# electrotactile_adapter.net
KiCad netlist of a schematic drawn in EAGLE
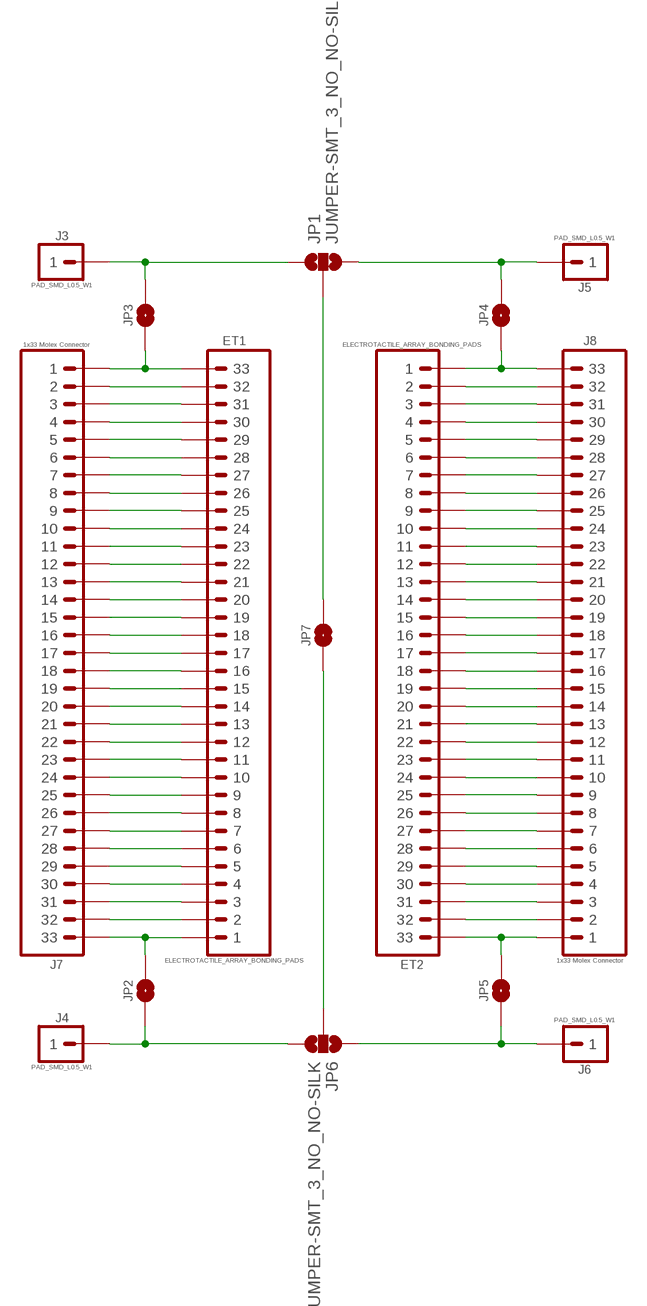
[diagram p0: schematic, sheet 1]

(export (version "E")
  (design (tool "Eeschema 10.0.6"))
  (components
    (comp (ref "ET1")
      (value "ELECTROTACTILE_ARRAY_BONDING_PADS")
      (footprint "eagle-import:ELECTROTACTILE_ARRAY_BONDING_PADS")
      (libsource (lib "eagle-import") (part "ELECTROTACTILE_ARRAY_BONDING_PADS"))
    )
    (comp (ref "ET2")
      (value "ELECTROTACTILE_ARRAY_BONDING_PADS")
      (footprint "eagle-import:ELECTROTACTILE_ARRAY_BONDING_PADS")
      (libsource (lib "eagle-import") (part "ELECTROTACTILE_ARRAY_BONDING_PADS"))
    )
    (comp (ref "J3")
      (value "PAD_SMD_L0.5_W1")
      (footprint "eagle-import:1X01_SMD_L0.5-W1")
      (libsource (lib "eagle-import") (part "PAD_SMD_L0.5_W1"))
    )
    (comp (ref "J4")
      (value "PAD_SMD_L0.5_W1")
      (footprint "eagle-import:1X01_SMD_L0.5-W1")
      (libsource (lib "eagle-import") (part "PAD_SMD_L0.5_W1"))
    )
    (comp (ref "J5")
      (value "PAD_SMD_L0.5_W1")
      (footprint "eagle-import:1X01_SMD_L0.5-W1")
      (libsource (lib "eagle-import") (part "PAD_SMD_L0.5_W1"))
    )
    (comp (ref "J6")
      (value "PAD_SMD_L0.5_W1")
      (footprint "eagle-import:1X01_SMD_L0.5-W1")
      (libsource (lib "eagle-import") (part "PAD_SMD_L0.5_W1"))
    )
    (comp (ref "J7")
      (value "1x33 Molex Connector")
      (footprint "eagle-import:_MOLEX-5025983393_FPC_PITCH-0.3MM")
      (fields (field (name "MFR") "Molex, LLC") (field (name "MPN") "5025983393"))
      (libsource (lib "eagle-import") (part "1X33_MOLEX_FPC_FPC_RIBBON-CABLE"))
    )
    (comp (ref "J8")
      (value "1x33 Molex Connector")
      (footprint "eagle-import:_MOLEX-5025983393_FPC_PITCH-0.3MM")
      (fields (field (name "MFR") "Molex, LLC") (field (name "MPN") "5025983393"))
      (libsource (lib "eagle-import") (part "1X33_MOLEX_FPC_FPC_RIBBON-CABLE"))
    )
    (comp (ref "JP1")
      (value "JUMPER-SMT_3_NO_NO-SILK")
      (footprint "eagle-import:SMT-JUMPER_3_NO_NO-SILK")
      (libsource (lib "eagle-import") (part "JUMPER-SMT_3_NO_NO-SILK"))
    )
    (comp (ref "JP2")
      (value "JUMPER_SMD_2-PAD_NO_SILK")
      (footprint "eagle-import:SMT-JUMPER_2_NO_SILK")
      (libsource (lib "eagle-import") (part "JUMPER_SMD_2-PAD_NO_SILK"))
    )
    (comp (ref "JP3")
      (value "JUMPER_SMD_2-PAD_NO_SILK")
      (footprint "eagle-import:SMT-JUMPER_2_NO_SILK")
      (libsource (lib "eagle-import") (part "JUMPER_SMD_2-PAD_NO_SILK"))
    )
    (comp (ref "JP4")
      (value "JUMPER_SMD_2-PAD_NO_SILK")
      (footprint "eagle-import:SMT-JUMPER_2_NO_SILK")
      (libsource (lib "eagle-import") (part "JUMPER_SMD_2-PAD_NO_SILK"))
    )
    (comp (ref "JP5")
      (value "JUMPER_SMD_2-PAD_NO_SILK")
      (footprint "eagle-import:SMT-JUMPER_2_NO_SILK")
      (libsource (lib "eagle-import") (part "JUMPER_SMD_2-PAD_NO_SILK"))
    )
    (comp (ref "JP6")
      (value "JUMPER-SMT_3_NO_NO-SILK")
      (footprint "eagle-import:SMT-JUMPER_3_NO_NO-SILK")
      (libsource (lib "eagle-import") (part "JUMPER-SMT_3_NO_NO-SILK"))
    )
    (comp (ref "JP7")
      (value "JUMPER_SMD_2-PAD_NO_SILK")
      (footprint "eagle-import:SMT-JUMPER_2_NO_SILK")
      (libsource (lib "eagle-import") (part "JUMPER_SMD_2-PAD_NO_SILK"))
    )
  )
  (nets
    (net (code "1") (name "Net-(ET1-1)") (class "Default")
      (node (ref "ET1") (pin "P$1") (pinfunction "1_P$1") (pintype "passive"))
      (node (ref "J7") (pin "P$33") (pinfunction "33_P$33") (pintype "passive"))
      (node (ref "JP2") (pin "2") (pinfunction "2_2") (pintype "passive"))
    )
    (net (code "2") (name "Net-(ET1-2)") (class "Default")
      (node (ref "ET1") (pin "P$2") (pinfunction "2_P$2") (pintype "passive"))
      (node (ref "J7") (pin "P$32") (pinfunction "32_P$32") (pintype "passive"))
    )
    (net (code "3") (name "Net-(ET1-3)") (class "Default")
      (node (ref "ET1") (pin "P$3") (pinfunction "3_P$3") (pintype "passive"))
      (node (ref "J7") (pin "P$31") (pinfunction "31_P$31") (pintype "passive"))
    )
    (net (code "4") (name "Net-(ET1-4)") (class "Default")
      (node (ref "ET1") (pin "P$4") (pinfunction "4_P$4") (pintype "passive"))
      (node (ref "J7") (pin "P$30") (pinfunction "30_P$30") (pintype "passive"))
    )
    (net (code "5") (name "Net-(ET1-5)") (class "Default")
      (node (ref "ET1") (pin "P$5") (pinfunction "5_P$5") (pintype "passive"))
      (node (ref "J7") (pin "P$29") (pinfunction "29_P$29") (pintype "passive"))
    )
    (net (code "6") (name "Net-(ET1-6)") (class "Default")
      (node (ref "ET1") (pin "P$6") (pinfunction "6_P$6") (pintype "passive"))
      (node (ref "J7") (pin "P$28") (pinfunction "28_P$28") (pintype "passive"))
    )
    (net (code "7") (name "Net-(ET1-7)") (class "Default")
      (node (ref "ET1") (pin "P$7") (pinfunction "7_P$7") (pintype "passive"))
      (node (ref "J7") (pin "P$27") (pinfunction "27_P$27") (pintype "passive"))
    )
    (net (code "8") (name "Net-(ET1-8)") (class "Default")
      (node (ref "ET1") (pin "P$8") (pinfunction "8_P$8") (pintype "passive"))
      (node (ref "J7") (pin "P$26") (pinfunction "26_P$26") (pintype "passive"))
    )
    (net (code "9") (name "Net-(ET1-9)") (class "Default")
      (node (ref "ET1") (pin "P$9") (pinfunction "9_P$9") (pintype "passive"))
      (node (ref "J7") (pin "P$25") (pinfunction "25_P$25") (pintype "passive"))
    )
    (net (code "10") (name "Net-(ET1-10)") (class "Default")
      (node (ref "ET1") (pin "P$10") (pinfunction "10_P$10") (pintype "passive"))
      (node (ref "J7") (pin "P$24") (pinfunction "24_P$24") (pintype "passive"))
    )
    (net (code "11") (name "Net-(ET1-11)") (class "Default")
      (node (ref "ET1") (pin "P$11") (pinfunction "11_P$11") (pintype "passive"))
      (node (ref "J7") (pin "P$23") (pinfunction "23_P$23") (pintype "passive"))
    )
    (net (code "12") (name "Net-(ET1-12)") (class "Default")
      (node (ref "ET1") (pin "P$12") (pinfunction "12_P$12") (pintype "passive"))
      (node (ref "J7") (pin "P$22") (pinfunction "22_P$22") (pintype "passive"))
    )
    (net (code "13") (name "Net-(ET1-13)") (class "Default")
      (node (ref "ET1") (pin "P$13") (pinfunction "13_P$13") (pintype "passive"))
      (node (ref "J7") (pin "P$21") (pinfunction "21_P$21") (pintype "passive"))
    )
    (net (code "14") (name "Net-(ET1-14)") (class "Default")
      (node (ref "ET1") (pin "P$14") (pinfunction "14_P$14") (pintype "passive"))
      (node (ref "J7") (pin "P$20") (pinfunction "20_P$20") (pintype "passive"))
    )
    (net (code "15") (name "Net-(ET1-15)") (class "Default")
      (node (ref "ET1") (pin "P$15") (pinfunction "15_P$15") (pintype "passive"))
      (node (ref "J7") (pin "P$19") (pinfunction "19_P$19") (pintype "passive"))
    )
    (net (code "16") (name "Net-(ET1-16)") (class "Default")
      (node (ref "ET1") (pin "P$16") (pinfunction "16_P$16") (pintype "passive"))
      (node (ref "J7") (pin "P$18") (pinfunction "18_P$18") (pintype "passive"))
    )
    (net (code "17") (name "Net-(ET1-17)") (class "Default")
      (node (ref "ET1") (pin "P$17") (pinfunction "17_P$17") (pintype "passive"))
      (node (ref "J7") (pin "P$17") (pinfunction "17_P$17") (pintype "passive"))
    )
    (net (code "18") (name "Net-(ET1-18)") (class "Default")
      (node (ref "ET1") (pin "P$18") (pinfunction "18_P$18") (pintype "passive"))
      (node (ref "J7") (pin "P$16") (pinfunction "16_P$16") (pintype "passive"))
    )
    (net (code "19") (name "Net-(ET1-19)") (class "Default")
      (node (ref "ET1") (pin "P$19") (pinfunction "19_P$19") (pintype "passive"))
      (node (ref "J7") (pin "P$15") (pinfunction "15_P$15") (pintype "passive"))
    )
    (net (code "20") (name "Net-(ET1-20)") (class "Default")
      (node (ref "ET1") (pin "P$20") (pinfunction "20_P$20") (pintype "passive"))
      (node (ref "J7") (pin "P$14") (pinfunction "14_P$14") (pintype "passive"))
    )
    (net (code "21") (name "Net-(ET1-21)") (class "Default")
      (node (ref "ET1") (pin "P$21") (pinfunction "21_P$21") (pintype "passive"))
      (node (ref "J7") (pin "P$13") (pinfunction "13_P$13") (pintype "passive"))
    )
    (net (code "22") (name "Net-(ET1-22)") (class "Default")
      (node (ref "ET1") (pin "P$22") (pinfunction "22_P$22") (pintype "passive"))
      (node (ref "J7") (pin "P$12") (pinfunction "12_P$12") (pintype "passive"))
    )
    (net (code "23") (name "Net-(ET1-23)") (class "Default")
      (node (ref "ET1") (pin "P$23") (pinfunction "23_P$23") (pintype "passive"))
      (node (ref "J7") (pin "P$11") (pinfunction "11_P$11") (pintype "passive"))
    )
    (net (code "24") (name "Net-(ET1-24)") (class "Default")
      (node (ref "ET1") (pin "P$24") (pinfunction "24_P$24") (pintype "passive"))
      (node (ref "J7") (pin "P$10") (pinfunction "10_P$10") (pintype "passive"))
    )
    (net (code "25") (name "Net-(ET1-25)") (class "Default")
      (node (ref "ET1") (pin "P$25") (pinfunction "25_P$25") (pintype "passive"))
      (node (ref "J7") (pin "P$9") (pinfunction "9_P$9") (pintype "passive"))
    )
    (net (code "26") (name "Net-(ET1-26)") (class "Default")
      (node (ref "ET1") (pin "P$26") (pinfunction "26_P$26") (pintype "passive"))
      (node (ref "J7") (pin "P$8") (pinfunction "8_P$8") (pintype "passive"))
    )
    (net (code "27") (name "Net-(ET1-27)") (class "Default")
      (node (ref "ET1") (pin "P$27") (pinfunction "27_P$27") (pintype "passive"))
      (node (ref "J7") (pin "P$7") (pinfunction "7_P$7") (pintype "passive"))
    )
    (net (code "28") (name "Net-(ET1-28)") (class "Default")
      (node (ref "ET1") (pin "P$28") (pinfunction "28_P$28") (pintype "passive"))
      (node (ref "J7") (pin "P$6") (pinfunction "6_P$6") (pintype "passive"))
    )
    (net (code "29") (name "Net-(ET1-29)") (class "Default")
      (node (ref "ET1") (pin "P$29") (pinfunction "29_P$29") (pintype "passive"))
      (node (ref "J7") (pin "P$5") (pinfunction "5_P$5") (pintype "passive"))
    )
    (net (code "30") (name "Net-(ET1-30)") (class "Default")
      (node (ref "ET1") (pin "P$30") (pinfunction "30_P$30") (pintype "passive"))
      (node (ref "J7") (pin "P$4") (pinfunction "4_P$4") (pintype "passive"))
    )
    (net (code "31") (name "Net-(ET1-31)") (class "Default")
      (node (ref "ET1") (pin "P$31") (pinfunction "31_P$31") (pintype "passive"))
      (node (ref "J7") (pin "P$3") (pinfunction "3_P$3") (pintype "passive"))
    )
    (net (code "32") (name "Net-(ET1-32)") (class "Default")
      (node (ref "ET1") (pin "P$32") (pinfunction "32_P$32") (pintype "passive"))
      (node (ref "J7") (pin "P$2") (pinfunction "2_P$2") (pintype "passive"))
    )
    (net (code "33") (name "Net-(ET1-33)") (class "Default")
      (node (ref "ET1") (pin "P$33") (pinfunction "33_P$33") (pintype "passive"))
      (node (ref "J7") (pin "P$1") (pinfunction "1_P$1") (pintype "passive"))
      (node (ref "JP3") (pin "1") (pinfunction "1_1") (pintype "passive"))
    )
    (net (code "34") (name "Net-(ET2-1)") (class "Default")
      (node (ref "ET2") (pin "P$1") (pinfunction "1_P$1") (pintype "passive"))
      (node (ref "J8") (pin "P$33") (pinfunction "33_P$33") (pintype "passive"))
      (node (ref "JP4") (pin "1") (pinfunction "1_1") (pintype "passive"))
    )
    (net (code "35") (name "Net-(ET2-2)") (class "Default")
      (node (ref "ET2") (pin "P$2") (pinfunction "2_P$2") (pintype "passive"))
      (node (ref "J8") (pin "P$32") (pinfunction "32_P$32") (pintype "passive"))
    )
    (net (code "36") (name "Net-(ET2-3)") (class "Default")
      (node (ref "ET2") (pin "P$3") (pinfunction "3_P$3") (pintype "passive"))
      (node (ref "J8") (pin "P$31") (pinfunction "31_P$31") (pintype "passive"))
    )
    (net (code "37") (name "Net-(ET2-4)") (class "Default")
      (node (ref "ET2") (pin "P$4") (pinfunction "4_P$4") (pintype "passive"))
      (node (ref "J8") (pin "P$30") (pinfunction "30_P$30") (pintype "passive"))
    )
    (net (code "38") (name "Net-(ET2-5)") (class "Default")
      (node (ref "ET2") (pin "P$5") (pinfunction "5_P$5") (pintype "passive"))
      (node (ref "J8") (pin "P$29") (pinfunction "29_P$29") (pintype "passive"))
    )
    (net (code "39") (name "Net-(ET2-6)") (class "Default")
      (node (ref "ET2") (pin "P$6") (pinfunction "6_P$6") (pintype "passive"))
      (node (ref "J8") (pin "P$28") (pinfunction "28_P$28") (pintype "passive"))
    )
    (net (code "40") (name "Net-(ET2-7)") (class "Default")
      (node (ref "ET2") (pin "P$7") (pinfunction "7_P$7") (pintype "passive"))
      (node (ref "J8") (pin "P$27") (pinfunction "27_P$27") (pintype "passive"))
    )
    (net (code "41") (name "Net-(ET2-8)") (class "Default")
      (node (ref "ET2") (pin "P$8") (pinfunction "8_P$8") (pintype "passive"))
      (node (ref "J8") (pin "P$26") (pinfunction "26_P$26") (pintype "passive"))
    )
    (net (code "42") (name "Net-(ET2-9)") (class "Default")
      (node (ref "ET2") (pin "P$9") (pinfunction "9_P$9") (pintype "passive"))
      (node (ref "J8") (pin "P$25") (pinfunction "25_P$25") (pintype "passive"))
    )
    (net (code "43") (name "Net-(ET2-10)") (class "Default")
      (node (ref "ET2") (pin "P$10") (pinfunction "10_P$10") (pintype "passive"))
      (node (ref "J8") (pin "P$24") (pinfunction "24_P$24") (pintype "passive"))
    )
    (net (code "44") (name "Net-(ET2-11)") (class "Default")
      (node (ref "ET2") (pin "P$11") (pinfunction "11_P$11") (pintype "passive"))
      (node (ref "J8") (pin "P$23") (pinfunction "23_P$23") (pintype "passive"))
    )
    (net (code "45") (name "Net-(ET2-12)") (class "Default")
      (node (ref "ET2") (pin "P$12") (pinfunction "12_P$12") (pintype "passive"))
      (node (ref "J8") (pin "P$22") (pinfunction "22_P$22") (pintype "passive"))
    )
    (net (code "46") (name "Net-(ET2-13)") (class "Default")
      (node (ref "ET2") (pin "P$13") (pinfunction "13_P$13") (pintype "passive"))
      (node (ref "J8") (pin "P$21") (pinfunction "21_P$21") (pintype "passive"))
    )
    (net (code "47") (name "Net-(ET2-14)") (class "Default")
      (node (ref "ET2") (pin "P$14") (pinfunction "14_P$14") (pintype "passive"))
      (node (ref "J8") (pin "P$20") (pinfunction "20_P$20") (pintype "passive"))
    )
    (net (code "48") (name "Net-(ET2-15)") (class "Default")
      (node (ref "ET2") (pin "P$15") (pinfunction "15_P$15") (pintype "passive"))
      (node (ref "J8") (pin "P$19") (pinfunction "19_P$19") (pintype "passive"))
    )
    (net (code "49") (name "Net-(ET2-16)") (class "Default")
      (node (ref "ET2") (pin "P$16") (pinfunction "16_P$16") (pintype "passive"))
      (node (ref "J8") (pin "P$18") (pinfunction "18_P$18") (pintype "passive"))
    )
    (net (code "50") (name "Net-(ET2-17)") (class "Default")
      (node (ref "ET2") (pin "P$17") (pinfunction "17_P$17") (pintype "passive"))
      (node (ref "J8") (pin "P$17") (pinfunction "17_P$17") (pintype "passive"))
    )
    (net (code "51") (name "Net-(ET2-18)") (class "Default")
      (node (ref "ET2") (pin "P$18") (pinfunction "18_P$18") (pintype "passive"))
      (node (ref "J8") (pin "P$16") (pinfunction "16_P$16") (pintype "passive"))
    )
    (net (code "52") (name "Net-(ET2-19)") (class "Default")
      (node (ref "ET2") (pin "P$19") (pinfunction "19_P$19") (pintype "passive"))
      (node (ref "J8") (pin "P$15") (pinfunction "15_P$15") (pintype "passive"))
    )
    (net (code "53") (name "Net-(ET2-20)") (class "Default")
      (node (ref "ET2") (pin "P$20") (pinfunction "20_P$20") (pintype "passive"))
      (node (ref "J8") (pin "P$14") (pinfunction "14_P$14") (pintype "passive"))
    )
    (net (code "54") (name "Net-(ET2-21)") (class "Default")
      (node (ref "ET2") (pin "P$21") (pinfunction "21_P$21") (pintype "passive"))
      (node (ref "J8") (pin "P$13") (pinfunction "13_P$13") (pintype "passive"))
    )
    (net (code "55") (name "Net-(ET2-22)") (class "Default")
      (node (ref "ET2") (pin "P$22") (pinfunction "22_P$22") (pintype "passive"))
      (node (ref "J8") (pin "P$12") (pinfunction "12_P$12") (pintype "passive"))
    )
    (net (code "56") (name "Net-(ET2-23)") (class "Default")
      (node (ref "ET2") (pin "P$23") (pinfunction "23_P$23") (pintype "passive"))
      (node (ref "J8") (pin "P$11") (pinfunction "11_P$11") (pintype "passive"))
    )
    (net (code "57") (name "Net-(ET2-24)") (class "Default")
      (node (ref "ET2") (pin "P$24") (pinfunction "24_P$24") (pintype "passive"))
      (node (ref "J8") (pin "P$10") (pinfunction "10_P$10") (pintype "passive"))
    )
    (net (code "58") (name "Net-(ET2-25)") (class "Default")
      (node (ref "ET2") (pin "P$25") (pinfunction "25_P$25") (pintype "passive"))
      (node (ref "J8") (pin "P$9") (pinfunction "9_P$9") (pintype "passive"))
    )
    (net (code "59") (name "Net-(ET2-26)") (class "Default")
      (node (ref "ET2") (pin "P$26") (pinfunction "26_P$26") (pintype "passive"))
      (node (ref "J8") (pin "P$8") (pinfunction "8_P$8") (pintype "passive"))
    )
    (net (code "60") (name "Net-(ET2-27)") (class "Default")
      (node (ref "ET2") (pin "P$27") (pinfunction "27_P$27") (pintype "passive"))
      (node (ref "J8") (pin "P$7") (pinfunction "7_P$7") (pintype "passive"))
    )
    (net (code "61") (name "Net-(ET2-28)") (class "Default")
      (node (ref "ET2") (pin "P$28") (pinfunction "28_P$28") (pintype "passive"))
      (node (ref "J8") (pin "P$6") (pinfunction "6_P$6") (pintype "passive"))
    )
    (net (code "62") (name "Net-(ET2-29)") (class "Default")
      (node (ref "ET2") (pin "P$29") (pinfunction "29_P$29") (pintype "passive"))
      (node (ref "J8") (pin "P$5") (pinfunction "5_P$5") (pintype "passive"))
    )
    (net (code "63") (name "Net-(ET2-30)") (class "Default")
      (node (ref "ET2") (pin "P$30") (pinfunction "30_P$30") (pintype "passive"))
      (node (ref "J8") (pin "P$4") (pinfunction "4_P$4") (pintype "passive"))
    )
    (net (code "64") (name "Net-(ET2-31)") (class "Default")
      (node (ref "ET2") (pin "P$31") (pinfunction "31_P$31") (pintype "passive"))
      (node (ref "J8") (pin "P$3") (pinfunction "3_P$3") (pintype "passive"))
    )
    (net (code "65") (name "Net-(ET2-32)") (class "Default")
      (node (ref "ET2") (pin "P$32") (pinfunction "32_P$32") (pintype "passive"))
      (node (ref "J8") (pin "P$2") (pinfunction "2_P$2") (pintype "passive"))
    )
    (net (code "66") (name "Net-(ET2-33)") (class "Default")
      (node (ref "ET2") (pin "P$33") (pinfunction "33_P$33") (pintype "passive"))
      (node (ref "J8") (pin "P$1") (pinfunction "1_P$1") (pintype "passive"))
      (node (ref "JP5") (pin "2") (pinfunction "2_2") (pintype "passive"))
    )
    (net (code "67") (name "Net-(J3-1)") (class "Default")
      (node (ref "J3") (pin "P$1") (pinfunction "1_P$1") (pintype "passive"))
      (node (ref "JP1") (pin "1") (pinfunction "1_1") (pintype "passive"))
      (node (ref "JP3") (pin "2") (pinfunction "2_2") (pintype "passive"))
    )
    (net (code "68") (name "Net-(J4-1)") (class "Default")
      (node (ref "J4") (pin "P$1") (pinfunction "1_P$1") (pintype "passive"))
      (node (ref "JP2") (pin "1") (pinfunction "1_1") (pintype "passive"))
      (node (ref "JP6") (pin "3") (pinfunction "3_3") (pintype "passive"))
    )
    (net (code "69") (name "Net-(J5-1)") (class "Default")
      (node (ref "J5") (pin "P$1") (pinfunction "1_P$1") (pintype "passive"))
      (node (ref "JP1") (pin "3") (pinfunction "3_3") (pintype "passive"))
      (node (ref "JP4") (pin "2") (pinfunction "2_2") (pintype "passive"))
    )
    (net (code "70") (name "Net-(J6-1)") (class "Default")
      (node (ref "J6") (pin "P$1") (pinfunction "1_P$1") (pintype "passive"))
      (node (ref "JP5") (pin "1") (pinfunction "1_1") (pintype "passive"))
      (node (ref "JP6") (pin "1") (pinfunction "1_1") (pintype "passive"))
    )
    (net (code "71") (name "Net-(JP1-Pad2)") (class "Default")
      (node (ref "JP1") (pin "2") (pinfunction "2_2") (pintype "passive"))
      (node (ref "JP7") (pin "2") (pinfunction "2_2") (pintype "passive"))
    )
    (net (code "72") (name "Net-(JP6-Pad2)") (class "Default")
      (node (ref "JP6") (pin "2") (pinfunction "2_2") (pintype "passive"))
      (node (ref "JP7") (pin "1") (pinfunction "1_1") (pintype "passive"))
    )
  )
)
